# 05_-CPU-UART_SPI.net
KiCad netlist of a schematic drawn in Altium Designer
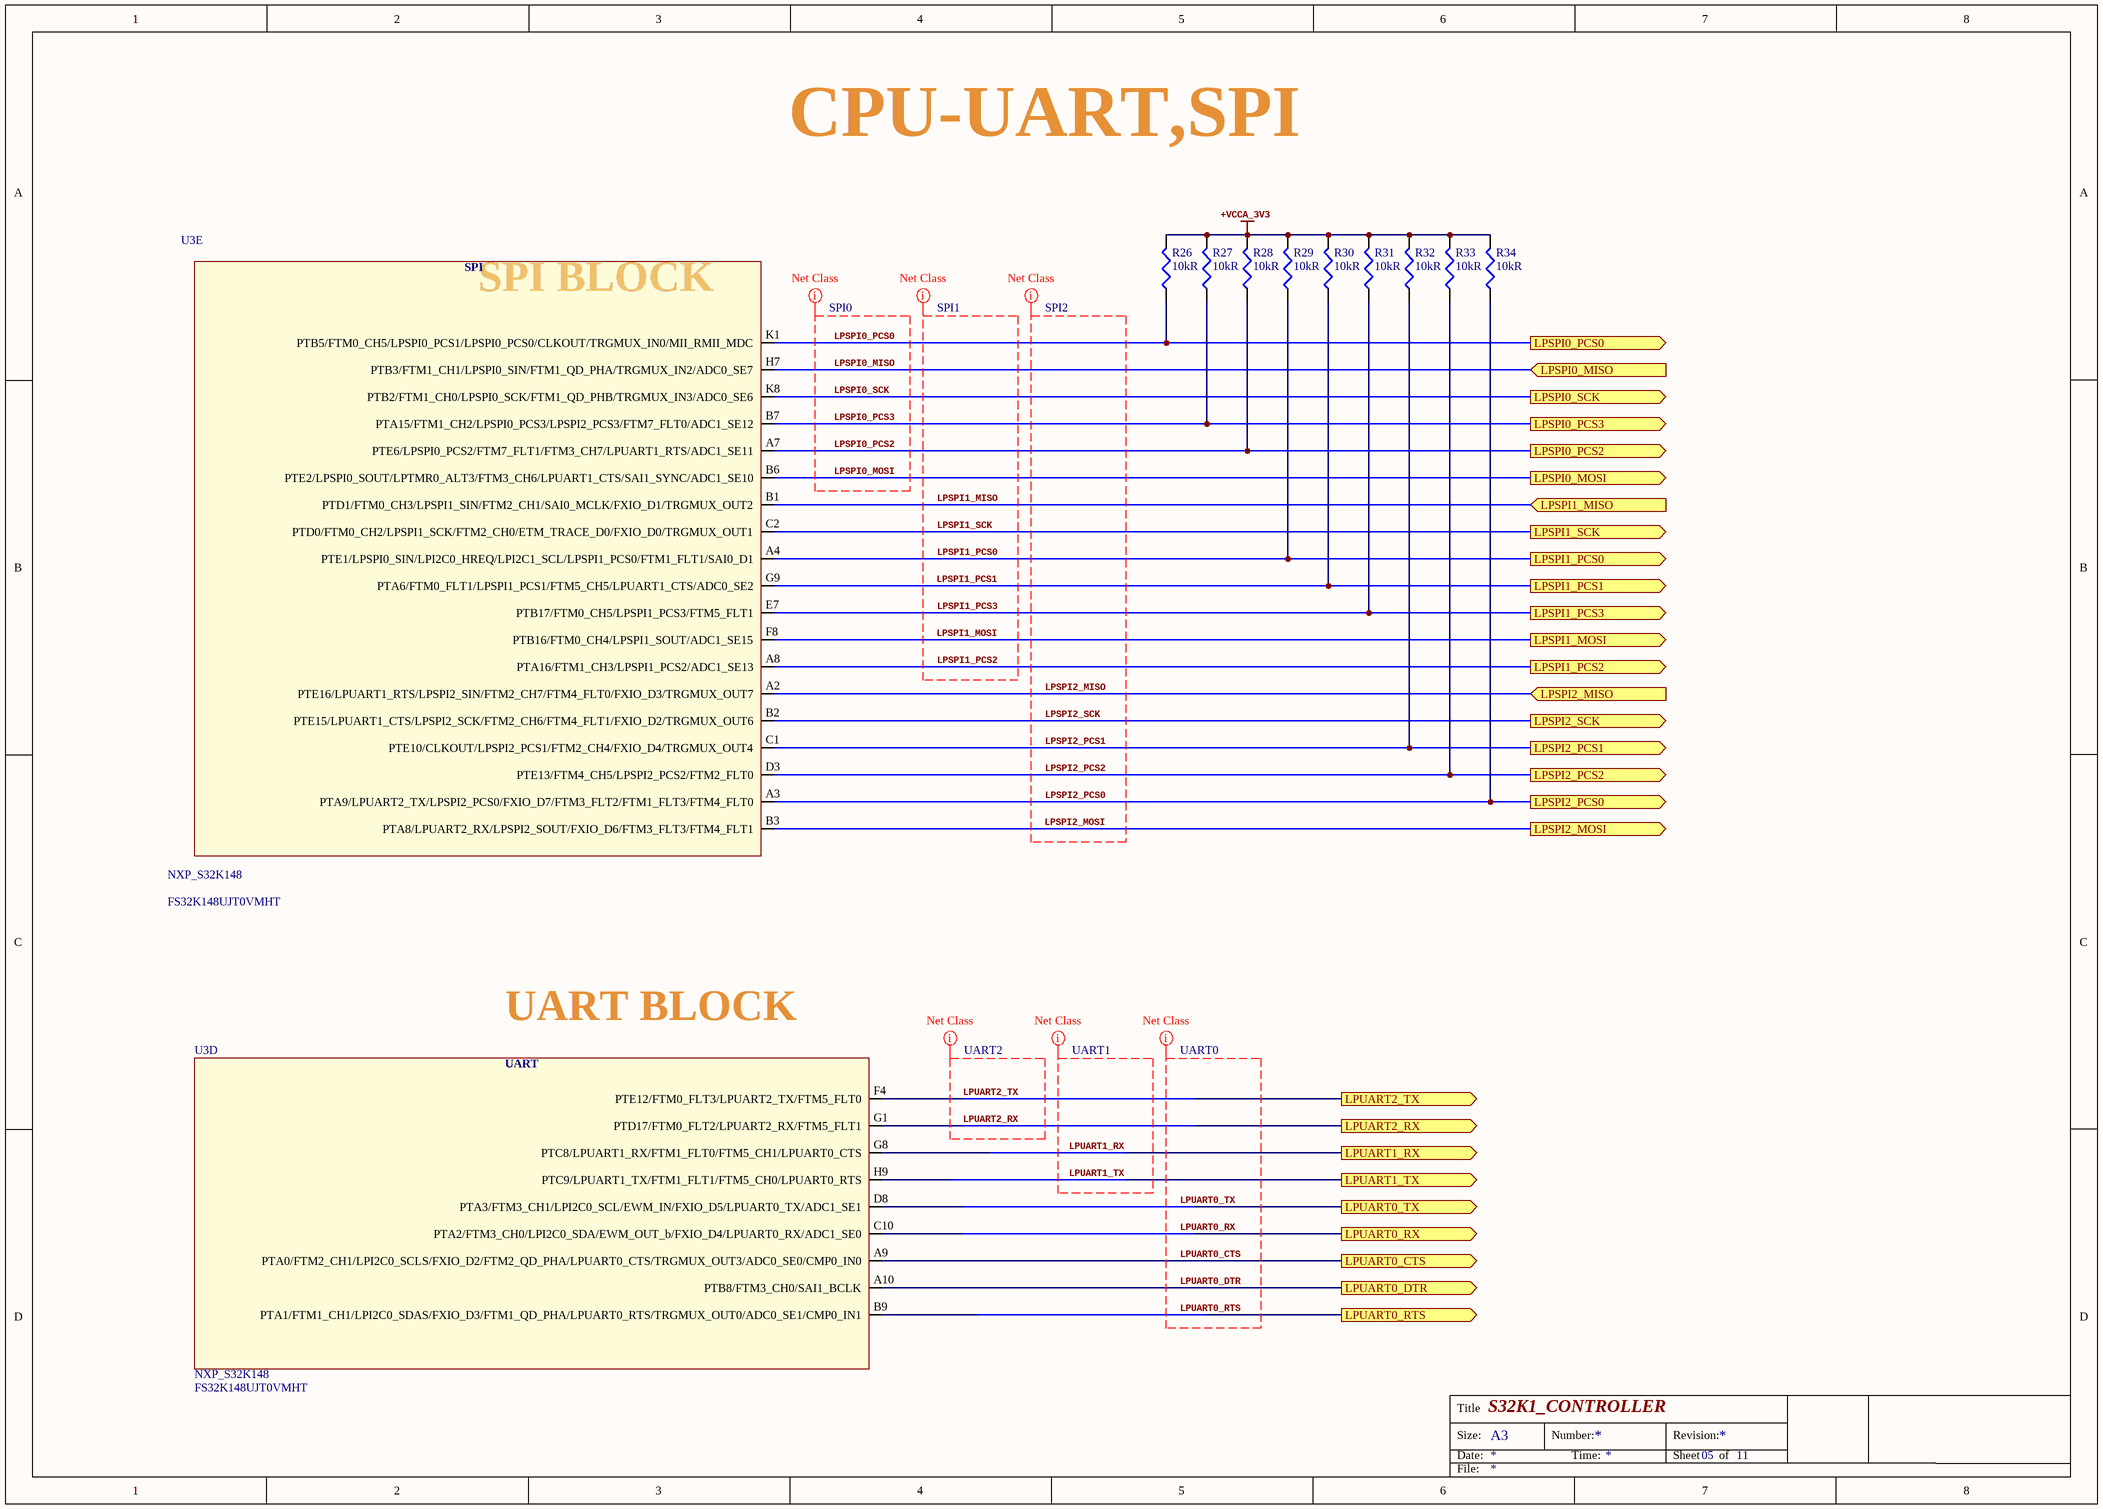
[diagram p0: [05]-CPU-UART,SPI.SchDoc]

(export (version "E")
  (design (tool "Eeschema 10.0.6"))
  (components
    (comp (ref "R26")
      (value "ERJ-2GEJ103X")
      (footprint "RES0402")
      (description "Res Thick Film 0402 10K Ohm 5% 1/10W ±200ppm/°C Molded SMD SMD Punched Carrier T/R")
      (fields
        (field (name "MANUFACTURER") "Panasonic")
        (field (name "TOLERANCE") "5%")
        (field (name "RESISTANCE") "10kR")
      )
      (libsource (lib "WeOnReferenceBoard") (part "ERJ-2GEJ103X"))
    )
    (comp (ref "R27")
      (value "ERJ-2GEJ103X")
      (footprint "RES0402")
      (description "Res Thick Film 0402 10K Ohm 5% 1/10W ±200ppm/°C Molded SMD SMD Punched Carrier T/R")
      (fields
        (field (name "MANUFACTURER") "Panasonic")
        (field (name "TOLERANCE") "5%")
        (field (name "RESISTANCE") "10kR")
      )
      (libsource (lib "WeOnReferenceBoard") (part "ERJ-2GEJ103X"))
    )
    (comp (ref "R28")
      (value "ERJ-2GEJ103X")
      (footprint "RES0402")
      (description "Res Thick Film 0402 10K Ohm 5% 1/10W ±200ppm/°C Molded SMD SMD Punched Carrier T/R")
      (fields
        (field (name "MANUFACTURER") "Panasonic")
        (field (name "TOLERANCE") "5%")
        (field (name "RESISTANCE") "10kR")
      )
      (libsource (lib "WeOnReferenceBoard") (part "ERJ-2GEJ103X"))
    )
    (comp (ref "R29")
      (value "ERJ-2GEJ103X")
      (footprint "RES0402")
      (description "Res Thick Film 0402 10K Ohm 5% 1/10W ±200ppm/°C Molded SMD SMD Punched Carrier T/R")
      (fields
        (field (name "MANUFACTURER") "Panasonic")
        (field (name "TOLERANCE") "5%")
        (field (name "RESISTANCE") "10kR")
      )
      (libsource (lib "WeOnReferenceBoard") (part "ERJ-2GEJ103X"))
    )
    (comp (ref "R30")
      (value "ERJ-2GEJ103X")
      (footprint "RES0402")
      (description "Res Thick Film 0402 10K Ohm 5% 1/10W ±200ppm/°C Molded SMD SMD Punched Carrier T/R")
      (fields
        (field (name "MANUFACTURER") "Panasonic")
        (field (name "TOLERANCE") "5%")
        (field (name "RESISTANCE") "10kR")
      )
      (libsource (lib "WeOnReferenceBoard") (part "ERJ-2GEJ103X"))
    )
    (comp (ref "R31")
      (value "ERJ-2GEJ103X")
      (footprint "RES0402")
      (description "Res Thick Film 0402 10K Ohm 5% 1/10W ±200ppm/°C Molded SMD SMD Punched Carrier T/R")
      (fields
        (field (name "MANUFACTURER") "Panasonic")
        (field (name "TOLERANCE") "5%")
        (field (name "RESISTANCE") "10kR")
      )
      (libsource (lib "WeOnReferenceBoard") (part "ERJ-2GEJ103X"))
    )
    (comp (ref "R32")
      (value "ERJ-2GEJ103X")
      (footprint "RES0402")
      (description "Res Thick Film 0402 10K Ohm 5% 1/10W ±200ppm/°C Molded SMD SMD Punched Carrier T/R")
      (fields
        (field (name "MANUFACTURER") "Panasonic")
        (field (name "TOLERANCE") "5%")
        (field (name "RESISTANCE") "10kR")
      )
      (libsource (lib "WeOnReferenceBoard") (part "ERJ-2GEJ103X"))
    )
    (comp (ref "R33")
      (value "ERJ-2GEJ103X")
      (footprint "RES0402")
      (description "Res Thick Film 0402 10K Ohm 5% 1/10W ±200ppm/°C Molded SMD SMD Punched Carrier T/R")
      (fields
        (field (name "MANUFACTURER") "Panasonic")
        (field (name "TOLERANCE") "5%")
        (field (name "RESISTANCE") "10kR")
      )
      (libsource (lib "WeOnReferenceBoard") (part "ERJ-2GEJ103X"))
    )
    (comp (ref "R34")
      (value "ERJ-2GEJ103X")
      (footprint "RES0402")
      (description "Res Thick Film 0402 10K Ohm 5% 1/10W ±200ppm/°C Molded SMD SMD Punched Carrier T/R")
      (fields
        (field (name "MANUFACTURER") "Panasonic")
        (field (name "TOLERANCE") "5%")
        (field (name "RESISTANCE") "10kR")
      )
      (libsource (lib "WeOnReferenceBoard") (part "ERJ-2GEJ103X"))
    )
    (comp (ref "U3")
      (value "NXP_S32K148")
      (footprint "WEONREFERENCEPLATFORM_100MAPBGA")
      (fields
        (field (name "MANUFACTURER") "NXP Semiconductors")
        (field (name "MANUFACTURER PART NUMBER") "FS32K148UJT0VMHT")
      )
      (libsource (lib "WeOnReferenceBoard") (part "NXP_S32K148"))
    )
  )
  (nets
    (net (code "1") (name "+VCCA_3V3") (class "Default")
      (node (ref "R26") (pin "2") (pinfunction "2_2") (pintype "passive"))
      (node (ref "R27") (pin "2") (pinfunction "2_2") (pintype "passive"))
      (node (ref "R28") (pin "2") (pinfunction "2_2") (pintype "passive"))
      (node (ref "R29") (pin "2") (pinfunction "2_2") (pintype "passive"))
      (node (ref "R30") (pin "2") (pinfunction "2_2") (pintype "passive"))
      (node (ref "R31") (pin "2") (pinfunction "2_2") (pintype "passive"))
      (node (ref "R32") (pin "2") (pinfunction "2_2") (pintype "passive"))
      (node (ref "R33") (pin "2") (pinfunction "2_2") (pintype "passive"))
      (node (ref "R34") (pin "2") (pinfunction "2_2") (pintype "passive"))
    )
    (net (code "2") (name "/LPSPI0_MISO") (class "Default")
      (node (ref "U3") (pin "H7") (pinfunction "PTB3/FTM1_CH1/LPSPI0_SIN/FTM1_QD_PHA/TRGMUX_IN2/ADC0_SE7_H7") (pintype "passive"))
    )
    (net (code "3") (name "/LPSPI0_MOSI") (class "Default")
      (node (ref "U3") (pin "B6") (pinfunction "PTE2/LPSPI0_SOUT/LPTMR0_ALT3/FTM3_CH6/LPUART1_CTS/SAI1_SYNC/ADC1_SE10_B6") (pintype "passive"))
    )
    (net (code "4") (name "/LPSPI0_PCS0") (class "Default")
      (node (ref "R26") (pin "1") (pinfunction "1_1") (pintype "passive"))
      (node (ref "U3") (pin "K1") (pinfunction "PTB5/FTM0_CH5/LPSPI0_PCS1/LPSPI0_PCS0/CLKOUT/TRGMUX_IN0/MII_RMII_MDC_K1") (pintype "passive"))
    )
    (net (code "5") (name "/LPSPI0_PCS2") (class "Default")
      (node (ref "R28") (pin "1") (pinfunction "1_1") (pintype "passive"))
      (node (ref "U3") (pin "A7") (pinfunction "PTE6/LPSPI0_PCS2/FTM7_FLT1/FTM3_CH7/LPUART1_RTS/ADC1_SE11_A7") (pintype "passive"))
    )
    (net (code "6") (name "/LPSPI0_PCS3") (class "Default")
      (node (ref "R27") (pin "1") (pinfunction "1_1") (pintype "passive"))
      (node (ref "U3") (pin "B7") (pinfunction "PTA15/FTM1_CH2/LPSPI0_PCS3/LPSPI2_PCS3/FTM7_FLT0/ADC1_SE12_B7") (pintype "passive"))
    )
    (net (code "7") (name "/LPSPI0_SCK") (class "Default")
      (node (ref "U3") (pin "K8") (pinfunction "PTB2/FTM1_CH0/LPSPI0_SCK/FTM1_QD_PHB/TRGMUX_IN3/ADC0_SE6_K8") (pintype "passive"))
    )
    (net (code "8") (name "/LPSPI1_MISO") (class "Default")
      (node (ref "U3") (pin "B1") (pinfunction "PTD1/FTM0_CH3/LPSPI1_SIN/FTM2_CH1/SAI0_MCLK/FXIO_D1/TRGMUX_OUT2_B1") (pintype "passive"))
    )
    (net (code "9") (name "/LPSPI1_MOSI") (class "Default")
      (node (ref "U3") (pin "F8") (pinfunction "PTB16/FTM0_CH4/LPSPI1_SOUT/ADC1_SE15_F8") (pintype "passive"))
    )
    (net (code "10") (name "/LPSPI1_PCS0") (class "Default")
      (node (ref "R29") (pin "1") (pinfunction "1_1") (pintype "passive"))
      (node (ref "U3") (pin "A4") (pinfunction "PTE1/LPSPI0_SIN/LPI2C0_HREQ/LPI2C1_SCL/LPSPI1_PCS0/FTM1_FLT1/SAI0_D1_A4") (pintype "passive"))
    )
    (net (code "11") (name "/LPSPI1_PCS1") (class "Default")
      (node (ref "R30") (pin "1") (pinfunction "1_1") (pintype "passive"))
      (node (ref "U3") (pin "G9") (pinfunction "PTA6/FTM0_FLT1/LPSPI1_PCS1/FTM5_CH5/LPUART1_CTS/ADC0_SE2_G9") (pintype "passive"))
    )
    (net (code "12") (name "/LPSPI1_PCS2") (class "Default")
      (node (ref "U3") (pin "A8") (pinfunction "PTA16/FTM1_CH3/LPSPI1_PCS2/ADC1_SE13_A8") (pintype "passive"))
    )
    (net (code "13") (name "/LPSPI1_PCS3") (class "Default")
      (node (ref "R31") (pin "1") (pinfunction "1_1") (pintype "passive"))
      (node (ref "U3") (pin "E7") (pinfunction "PTB17/FTM0_CH5/LPSPI1_PCS3/FTM5_FLT1_E7") (pintype "passive"))
    )
    (net (code "14") (name "/LPSPI1_SCK") (class "Default")
      (node (ref "U3") (pin "C2") (pinfunction "PTD0/FTM0_CH2/LPSPI1_SCK/FTM2_CH0/ETM_TRACE_D0/FXIO_D0/TRGMUX_OUT1_C2") (pintype "passive"))
    )
    (net (code "15") (name "/LPSPI2_MISO") (class "Default")
      (node (ref "U3") (pin "A2") (pinfunction "PTE16/LPUART1_RTS/LPSPI2_SIN/FTM2_CH7/FTM4_FLT0/FXIO_D3/TRGMUX_OUT7_A2") (pintype "passive"))
    )
    (net (code "16") (name "/LPSPI2_MOSI") (class "Default")
      (node (ref "U3") (pin "B3") (pinfunction "PTA8/LPUART2_RX/LPSPI2_SOUT/FXIO_D6/FTM3_FLT3/FTM4_FLT1_B3") (pintype "passive"))
    )
    (net (code "17") (name "/LPSPI2_PCS0") (class "Default")
      (node (ref "R34") (pin "1") (pinfunction "1_1") (pintype "passive"))
      (node (ref "U3") (pin "A3") (pinfunction "PTA9/LPUART2_TX/LPSPI2_PCS0/FXIO_D7/FTM3_FLT2/FTM1_FLT3/FTM4_FLT0_A3") (pintype "passive"))
    )
    (net (code "18") (name "/LPSPI2_PCS1") (class "Default")
      (node (ref "R32") (pin "1") (pinfunction "1_1") (pintype "passive"))
      (node (ref "U3") (pin "C1") (pinfunction "PTE10/CLKOUT/LPSPI2_PCS1/FTM2_CH4/FXIO_D4/TRGMUX_OUT4_C1") (pintype "passive"))
    )
    (net (code "19") (name "/LPSPI2_PCS2") (class "Default")
      (node (ref "R33") (pin "1") (pinfunction "1_1") (pintype "passive"))
      (node (ref "U3") (pin "D3") (pinfunction "PTE13/FTM4_CH5/LPSPI2_PCS2/FTM2_FLT0_D3") (pintype "passive"))
    )
    (net (code "20") (name "/LPSPI2_SCK") (class "Default")
      (node (ref "U3") (pin "B2") (pinfunction "PTE15/LPUART1_CTS/LPSPI2_SCK/FTM2_CH6/FTM4_FLT1/FXIO_D2/TRGMUX_OUT6_B2") (pintype "passive"))
    )
    (net (code "21") (name "/LPUART0_CTS") (class "Default")
      (node (ref "U3") (pin "A9") (pinfunction "PTA0/FTM2_CH1/LPI2C0_SCLS/FXIO_D2/FTM2_QD_PHA/LPUART0_CTS/TRGMUX_OUT3/ADC0_SE0/CMP0_IN0_A9") (pintype "passive"))
    )
    (net (code "22") (name "/LPUART0_DTR") (class "Default")
      (node (ref "U3") (pin "A10") (pinfunction "PTB8/FTM3_CH0/SAI1_BCLK_A10") (pintype "passive"))
    )
    (net (code "23") (name "/LPUART0_RTS") (class "Default")
      (node (ref "U3") (pin "B9") (pinfunction "PTA1/FTM1_CH1/LPI2C0_SDAS/FXIO_D3/FTM1_QD_PHA/LPUART0_RTS/TRGMUX_OUT0/ADC0_SE1/CMP0_IN1_B9") (pintype "passive"))
    )
    (net (code "24") (name "/LPUART0_RX") (class "Default")
      (node (ref "U3") (pin "C10") (pinfunction "PTA2/FTM3_CH0/LPI2C0_SDA/EWM_OUT_b/FXIO_D4/LPUART0_RX/ADC1_SE0_C10") (pintype "passive"))
    )
    (net (code "25") (name "/LPUART0_TX") (class "Default")
      (node (ref "U3") (pin "D8") (pinfunction "PTA3/FTM3_CH1/LPI2C0_SCL/EWM_IN/FXIO_D5/LPUART0_TX/ADC1_SE1_D8") (pintype "passive"))
    )
    (net (code "26") (name "/LPUART1_RX") (class "Default")
      (node (ref "U3") (pin "G8") (pinfunction "PTC8/LPUART1_RX/FTM1_FLT0/FTM5_CH1/LPUART0_CTS_G8") (pintype "passive"))
    )
    (net (code "27") (name "/LPUART1_TX") (class "Default")
      (node (ref "U3") (pin "H9") (pinfunction "PTC9/LPUART1_TX/FTM1_FLT1/FTM5_CH0/LPUART0_RTS_H9") (pintype "passive"))
    )
    (net (code "28") (name "/LPUART2_RX") (class "Default")
      (node (ref "U3") (pin "G1") (pinfunction "PTD17/FTM0_FLT2/LPUART2_RX/FTM5_FLT1_G1") (pintype "passive"))
    )
    (net (code "29") (name "/LPUART2_TX") (class "Default")
      (node (ref "U3") (pin "F4") (pinfunction "PTE12/FTM0_FLT3/LPUART2_TX/FTM5_FLT0_F4") (pintype "passive"))
    )
  )
)
